# Board.net
KiCad netlist of a schematic drawn in EAGLE
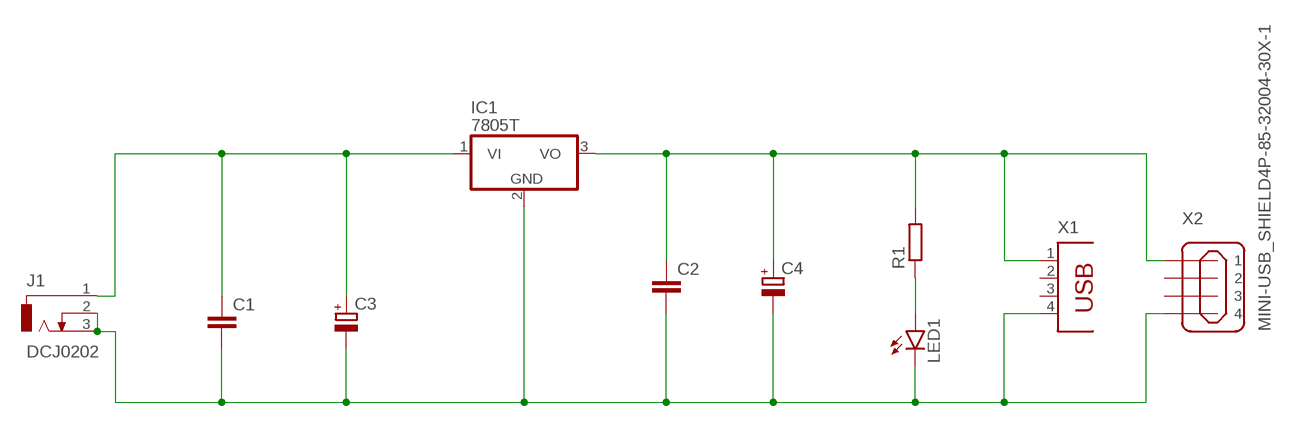
[diagram p0: schematic, sheet 1]

(export (version "E")
  (design (tool "Eeschema 10.0.6"))
  (components
    (comp (ref "C1")
      (value "C-EU025-024X044")
      (footprint "eagle-import:C025-024X044")
      (libsource (lib "eagle-import") (part "C-EU025-024X044"))
    )
    (comp (ref "C2")
      (value "C-EU025-024X044")
      (footprint "eagle-import:C025-024X044")
      (libsource (lib "eagle-import") (part "C-EU025-024X044"))
    )
    (comp (ref "C3")
      (value "CPOL-EUB45181A")
      (footprint "eagle-import:B45181A")
      (libsource (lib "eagle-import") (part "CPOL-EUB45181A"))
    )
    (comp (ref "C4")
      (value "CPOL-EUB45181A")
      (footprint "eagle-import:B45181A")
      (libsource (lib "eagle-import") (part "CPOL-EUB45181A"))
    )
    (comp (ref "IC1")
      (value "7805T")
      (footprint "eagle-import:TO220H")
      (libsource (lib "eagle-import") (part "78T05"))
    )
    (comp (ref "J1")
      (value "DCJ0202")
      (footprint "eagle-import:DCJ0202")
      (libsource (lib "eagle-import") (part "DCJ0202"))
    )
    (comp (ref "LED1")
      (value "LED5MM")
      (footprint "eagle-import:LED5MM")
      (libsource (lib "eagle-import") (part "LED5MM"))
    )
    (comp (ref "R1")
      (value "R-EU_0204/2V")
      (footprint "eagle-import:0204V")
      (libsource (lib "eagle-import") (part "R-EU_0204/2V"))
    )
    (comp (ref "X1")
      (value "PN61729")
      (footprint "eagle-import:PN61729")
      (libsource (lib "eagle-import") (part "PN61729"))
    )
    (comp (ref "X2")
      (value "MINI-USB_SHIELD4P-85-32004-30X-1")
      (footprint "eagle-import:85-32004-30X-1")
      (libsource (lib "eagle-import") (part "MINI-USB_SHIELD4P-85-32004-30X-1"))
    )
  )
  (nets
    (net (code "1") (name "Net-(IC1-GND)") (class "Default")
      (node (ref "C1") (pin "2") (pinfunction "2_2") (pintype "passive"))
      (node (ref "C2") (pin "2") (pinfunction "2_2") (pintype "passive"))
      (node (ref "C3") (pin "-") (pinfunction "-_-") (pintype "passive"))
      (node (ref "C4") (pin "-") (pinfunction "-_-") (pintype "passive"))
      (node (ref "IC1") (pin "2") (pinfunction "GND_2") (pintype "passive"))
      (node (ref "J1") (pin "2") (pinfunction "2_2") (pintype "passive"))
      (node (ref "J1") (pin "3") (pinfunction "3_3") (pintype "passive"))
      (node (ref "LED1") (pin "K") (pinfunction "C_K") (pintype "passive"))
      (node (ref "X1") (pin "4") (pinfunction "4_4") (pintype "passive"))
      (node (ref "X2") (pin "4") (pinfunction "4_4") (pintype "passive"))
    )
    (net (code "2") (name "Net-(IC1-VI)") (class "Default")
      (node (ref "C1") (pin "1") (pinfunction "1_1") (pintype "passive"))
      (node (ref "C3") (pin "+") (pinfunction "+_+") (pintype "passive"))
      (node (ref "IC1") (pin "1") (pinfunction "VI_1") (pintype "input"))
      (node (ref "J1") (pin "1") (pinfunction "1_1") (pintype "passive"))
    )
    (net (code "3") (name "Net-(IC1-VO)") (class "Default")
      (node (ref "C2") (pin "1") (pinfunction "1_1") (pintype "passive"))
      (node (ref "C4") (pin "+") (pinfunction "+_+") (pintype "passive"))
      (node (ref "IC1") (pin "3") (pinfunction "VO_3") (pintype "passive"))
      (node (ref "R1") (pin "2") (pinfunction "2_2") (pintype "passive"))
      (node (ref "X1") (pin "1") (pinfunction "1_1") (pintype "passive"))
      (node (ref "X2") (pin "1") (pinfunction "1_1") (pintype "passive"))
    )
    (net (code "4") (name "Net-(LED1-PadA)") (class "Default")
      (node (ref "LED1") (pin "A") (pinfunction "A_A") (pintype "passive"))
      (node (ref "R1") (pin "1") (pinfunction "1_1") (pintype "passive"))
    )
    (net (code "5") (name "unconnected-(X1-Pad2)") (class "Default")
      (node (ref "X1") (pin "2") (pinfunction "2_2") (pintype "passive"))
    )
    (net (code "6") (name "unconnected-(X1-Pad3)") (class "Default")
      (node (ref "X1") (pin "3") (pinfunction "3_3") (pintype "passive"))
    )
    (net (code "7") (name "unconnected-(X2-Pad2)") (class "Default")
      (node (ref "X2") (pin "2") (pinfunction "2_2") (pintype "passive"))
    )
    (net (code "8") (name "unconnected-(X2-Pad3)") (class "Default")
      (node (ref "X2") (pin "3") (pinfunction "3_3") (pintype "passive"))
    )
  )
)
